# EQULIZER.net
KiCad netlist of a schematic drawn in Altium Designer
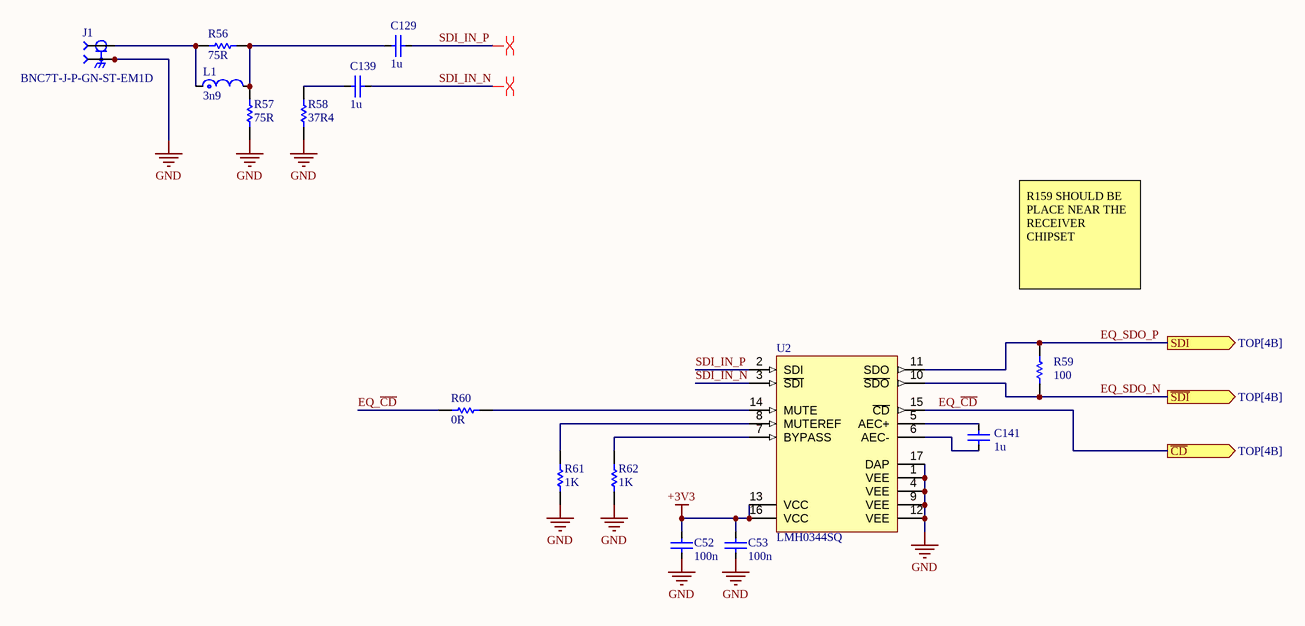
[diagram p0: EQULIZER.SchDoc]

(export (version "E")
  (design (tool "Eeschema 10.0.6"))
  (components
    (comp (ref "C52")
      (value "100n")
      (footprint "FP-C1005-050-0_05-IPC_C")
      (description "MLCC 100nF ±10% 50V X7R SMD 0402")
      (fields (field (name "VOLTAGE") "50V") (field (name "TOLERANCE") "10%"))
      (libsource (lib "Schlib1") (part "C1005X7R1H104K050BB"))
    )
    (comp (ref "C53")
      (value "100n")
      (footprint "FP-C1005-050-0_05-IPC_C")
      (description "MLCC 100nF ±10% 50V X7R SMD 0402")
      (fields (field (name "VOLTAGE") "50V") (field (name "TOLERANCE") "10%"))
      (libsource (lib "Schlib1") (part "C1005X7R1H104K050BB"))
    )
    (comp (ref "C129")
      (value "1u")
      (footprint "CAPC1005X55X10LL05")
      (description "MLCC 1 uF, +/- 10%, 10 V, -55 to 85 degC, 0402 (1005 Metric), RoHS, Tape and Reel")
      (fields (field (name "MANUFACTURER") "TDK") (field (name "TOLERANCE") "±10%"))
      (libsource (lib "Schlib1") (part "C1005X5R1A105K050BB"))
    )
    (comp (ref "C139")
      (value "1u")
      (footprint "CAPC1005X55X10LL05")
      (description "MLCC 1 uF, +/- 10%, 10 V, -55 to 85 degC, 0402 (1005 Metric), RoHS, Tape and Reel")
      (fields (field (name "MANUFACTURER") "TDK") (field (name "TOLERANCE") "±10%"))
      (libsource (lib "Schlib1") (part "C1005X5R1A105K050BB"))
    )
    (comp (ref "C141")
      (value "1u")
      (footprint "CAPC1005X55X10LL05")
      (description "MLCC 1 uF, +/- 10%, 10 V, -55 to 85 degC, 0402 (1005 Metric), RoHS, Tape and Reel")
      (fields (field (name "TOLERANCE") "±10%") (field (name "MANUFACTURER") "TDK"))
      (libsource (lib "Schlib1") (part "C1005X5R1A105K050BB"))
    )
    (comp (ref "J1")
      (value "BNC7T-J-P-GN-ST-EM1D")
      (footprint "SAMTEC_BNC7T-J-P-XX-ST-EM1D")
      (description "BNC Connector Jack, Female Socket 75Ohm Board Edge, End Launch; Panel Mount Solder")
      (fields (field (name "MF") "Samtec Inc."))
      (libsource (lib "Schlib1") (part "BNC7T-J-P-GN-ST-EM1D"))
    )
    (comp (ref "L1")
      (value "3n9")
      (footprint "FP-LQP03TG_02-IPC_C")
      (description "Film type RF Inductor 3.9nH ±0.1nH 400mA 0.3Ω 0201 (0603)")
      (fields (field (name "TOLERANCE") "3%") (field (name "Comment") "LQP03TN3N9B02D"))
      (libsource (lib "Schlib1") (part "LQP03TN3N9B02D"))
    )
    (comp (ref "R56")
      (value "75R")
      (footprint "pcblib1:RESC1005X40X25LL05T10")
      (fields (field (name "MANUFACTURER") "Yageo / Phycomp") (field (name "PART NUMBER") "RC0402FR-0775RL"))
      (libsource (lib "Schlib1") (part "RC0402FR-0775RL"))
    )
    (comp (ref "R57")
      (value "75R")
      (footprint "pcblib1:RESC1005X40X25LL05T10")
      (fields (field (name "MANUFACTURER") "Yageo / Phycomp") (field (name "PART NUMBER") "RC0402FR-0775RL"))
      (libsource (lib "Schlib1") (part "RC0402FR-0775RL"))
    )
    (comp (ref "R58")
      (value "37R4")
      (footprint "RESC1005X40X25LL05T10")
      (fields (field (name "MANUFACTURER") "Yageo / Phycomp") (field (name "PART NUMBER") "RC0402FR-0737R4L"))
      (libsource (lib "Schlib1") (part "RC0402FR-0737R4L"))
    )
    (comp (ref "R59")
      (value "100")
      (footprint "RESC1005X40X25LL05T10")
      (fields (field (name "PART NUMBER") "RC0402FR-07100RL") (field (name "MANUFACTURER") "Yageo / Phycomp"))
      (libsource (lib "Schlib1") (part "RC0402FR-07100RL"))
    )
    (comp (ref "R60")
      (value "0R")
      (footprint "RESC1005X40X25LL05T10")
      (description "RES 0R OHM 1% 1/16W 0402")
      (fields (field (name "MANUFACTURER") "Yageo / Phycomp") (field (name "PART NUMBER") "RC0402FR-070RL"))
      (libsource (lib "Schlib1") (part "RES"))
    )
    (comp (ref "R61")
      (value "1K")
      (footprint "RESC1005X40X25LL05T10")
      (description "RES 1K OHM 1% 1/16W 0402")
      (fields (field (name "MANUFACTURER") "Yageo / Phycomp") (field (name "PART NUMBER") "RC0402FR-0737R4L"))
      (libsource (lib "Schlib1") (part "RES"))
    )
    (comp (ref "R62")
      (value "1K")
      (footprint "RESC1005X40X25LL05T10")
      (description "RES 1K OHM 1% 1/16W 0402")
      (fields (field (name "MANUFACTURER") "Yageo / Phycomp") (field (name "PART NUMBER") "RC0402FR-0737R4L"))
      (libsource (lib "Schlib1") (part "RES"))
    )
    (comp (ref "U2")
      (value "LMH0344SQ")
      (footprint "pcblib1:SQB16A")
      (description "3 Gbps HD/SD SDI Adaptive Cable Equalizer, 16-pin LLP")
      (fields
        (field (name "MANUFACTURER") "National Semiconductor")
        (field (name "MANUFACTURER PART NUMBER") "RC0402FR-070RL")
      )
      (libsource (lib "Schlib1") (part "LMH0344SQ"))
    )
  )
  (nets
    (net (code "1") (name "+3V3") (class "Default")
      (node (ref "C52") (pin "1") (pinfunction "1_1") (pintype "passive"))
      (node (ref "C53") (pin "1") (pinfunction "1_1") (pintype "passive"))
      (node (ref "U2") (pin "13") (pinfunction "VCC_13") (pintype "power_in"))
      (node (ref "U2") (pin "16") (pinfunction "VCC_16") (pintype "power_in"))
    )
    (net (code "2") (name "/EQ_SDO_N") (class "Default")
      (node (ref "R59") (pin "2") (pinfunction "2_2") (pintype "passive"))
      (node (ref "U2") (pin "10") (pinfunction "~{SDO}_10") (pintype "output"))
    )
    (net (code "3") (name "/EQ_SDO_P") (class "Default")
      (node (ref "R59") (pin "1") (pinfunction "1_1") (pintype "passive"))
      (node (ref "U2") (pin "11") (pinfunction "SDO_11") (pintype "output"))
    )
    (net (code "4") (name "/EQ_~{CD}") (class "Default")
      (node (ref "R60") (pin "1") (pinfunction "1_1") (pintype "passive"))
      (node (ref "U2") (pin "15") (pinfunction "~{CD}_15") (pintype "output"))
    )
    (net (code "5") (name "/SDI_IN_N") (class "Default")
      (node (ref "C139") (pin "2") (pinfunction "2_2") (pintype "passive"))
      (node (ref "U2") (pin "3") (pinfunction "~{SDI}_3") (pintype "input"))
    )
    (net (code "6") (name "/SDI_IN_P") (class "Default")
      (node (ref "C129") (pin "2") (pinfunction "2_2") (pintype "passive"))
      (node (ref "U2") (pin "2") (pinfunction "SDI_2") (pintype "input"))
    )
    (net (code "7") (name "GND") (class "Default")
      (node (ref "C52") (pin "2") (pinfunction "2_2") (pintype "passive"))
      (node (ref "C53") (pin "2") (pinfunction "2_2") (pintype "passive"))
      (node (ref "J1") (pin "S1") (pinfunction "2_S1") (pintype "passive"))
      (node (ref "J1") (pin "S2") (pinfunction "2_S2") (pintype "passive"))
      (node (ref "J1") (pin "S3") (pinfunction "2_S3") (pintype "passive"))
      (node (ref "J1") (pin "S4") (pinfunction "2_S4") (pintype "passive"))
      (node (ref "R57") (pin "2") (pinfunction "2_2") (pintype "passive"))
      (node (ref "R58") (pin "2") (pinfunction "2_2") (pintype "passive"))
      (node (ref "R61") (pin "2") (pinfunction "2_2") (pintype "passive"))
      (node (ref "R62") (pin "2") (pinfunction "2_2") (pintype "passive"))
      (node (ref "U2") (pin "1") (pinfunction "VEE_1") (pintype "power_in"))
      (node (ref "U2") (pin "12") (pinfunction "VEE_12") (pintype "power_in"))
      (node (ref "U2") (pin "17") (pinfunction "DAP_17") (pintype "power_in"))
      (node (ref "U2") (pin "4") (pinfunction "VEE_4") (pintype "power_in"))
      (node (ref "U2") (pin "9") (pinfunction "VEE_9") (pintype "power_in"))
    )
    (net (code "8") (name "Net-(C129-Pad1)") (class "Default")
      (node (ref "C129") (pin "1") (pinfunction "1_1") (pintype "passive"))
      (node (ref "L1") (pin "2") (pinfunction "2_2") (pintype "passive"))
      (node (ref "R56") (pin "2") (pinfunction "2_2") (pintype "passive"))
      (node (ref "R57") (pin "1") (pinfunction "1_1") (pintype "passive"))
    )
    (net (code "9") (name "Net-(C139-Pad1)") (class "Default")
      (node (ref "C139") (pin "1") (pinfunction "1_1") (pintype "passive"))
      (node (ref "R58") (pin "1") (pinfunction "1_1") (pintype "passive"))
    )
    (net (code "10") (name "Net-(J1-Pad1)") (class "Default")
      (node (ref "J1") (pin "1") (pinfunction "1_1") (pintype "passive"))
      (node (ref "L1") (pin "1") (pinfunction "1_1") (pintype "passive"))
      (node (ref "R56") (pin "1") (pinfunction "1_1") (pintype "passive"))
    )
    (net (code "11") (name "Net-(U2-AEC+)") (class "Default")
      (node (ref "C141") (pin "1") (pinfunction "1_1") (pintype "passive"))
      (node (ref "U2") (pin "5") (pinfunction "AEC+_5") (pintype "passive"))
    )
    (net (code "12") (name "Net-(U2-AEC-)") (class "Default")
      (node (ref "C141") (pin "2") (pinfunction "2_2") (pintype "passive"))
      (node (ref "U2") (pin "6") (pinfunction "AEC-_6") (pintype "passive"))
    )
    (net (code "13") (name "Net-(U2-BYPASS)") (class "Default")
      (node (ref "R62") (pin "1") (pinfunction "1_1") (pintype "passive"))
      (node (ref "U2") (pin "7") (pinfunction "BYPASS_7") (pintype "input"))
    )
    (net (code "14") (name "Net-(U2-MUTE)") (class "Default")
      (node (ref "R60") (pin "2") (pinfunction "2_2") (pintype "passive"))
      (node (ref "U2") (pin "14") (pinfunction "MUTE_14") (pintype "input"))
    )
    (net (code "15") (name "Net-(U2-MUTEREF)") (class "Default")
      (node (ref "R61") (pin "1") (pinfunction "1_1") (pintype "passive"))
      (node (ref "U2") (pin "8") (pinfunction "MUTEREF_8") (pintype "input"))
    )
  )
)
